# L-D5019-01-05.net
KiCad netlist of a schematic drawn in Altium Designer
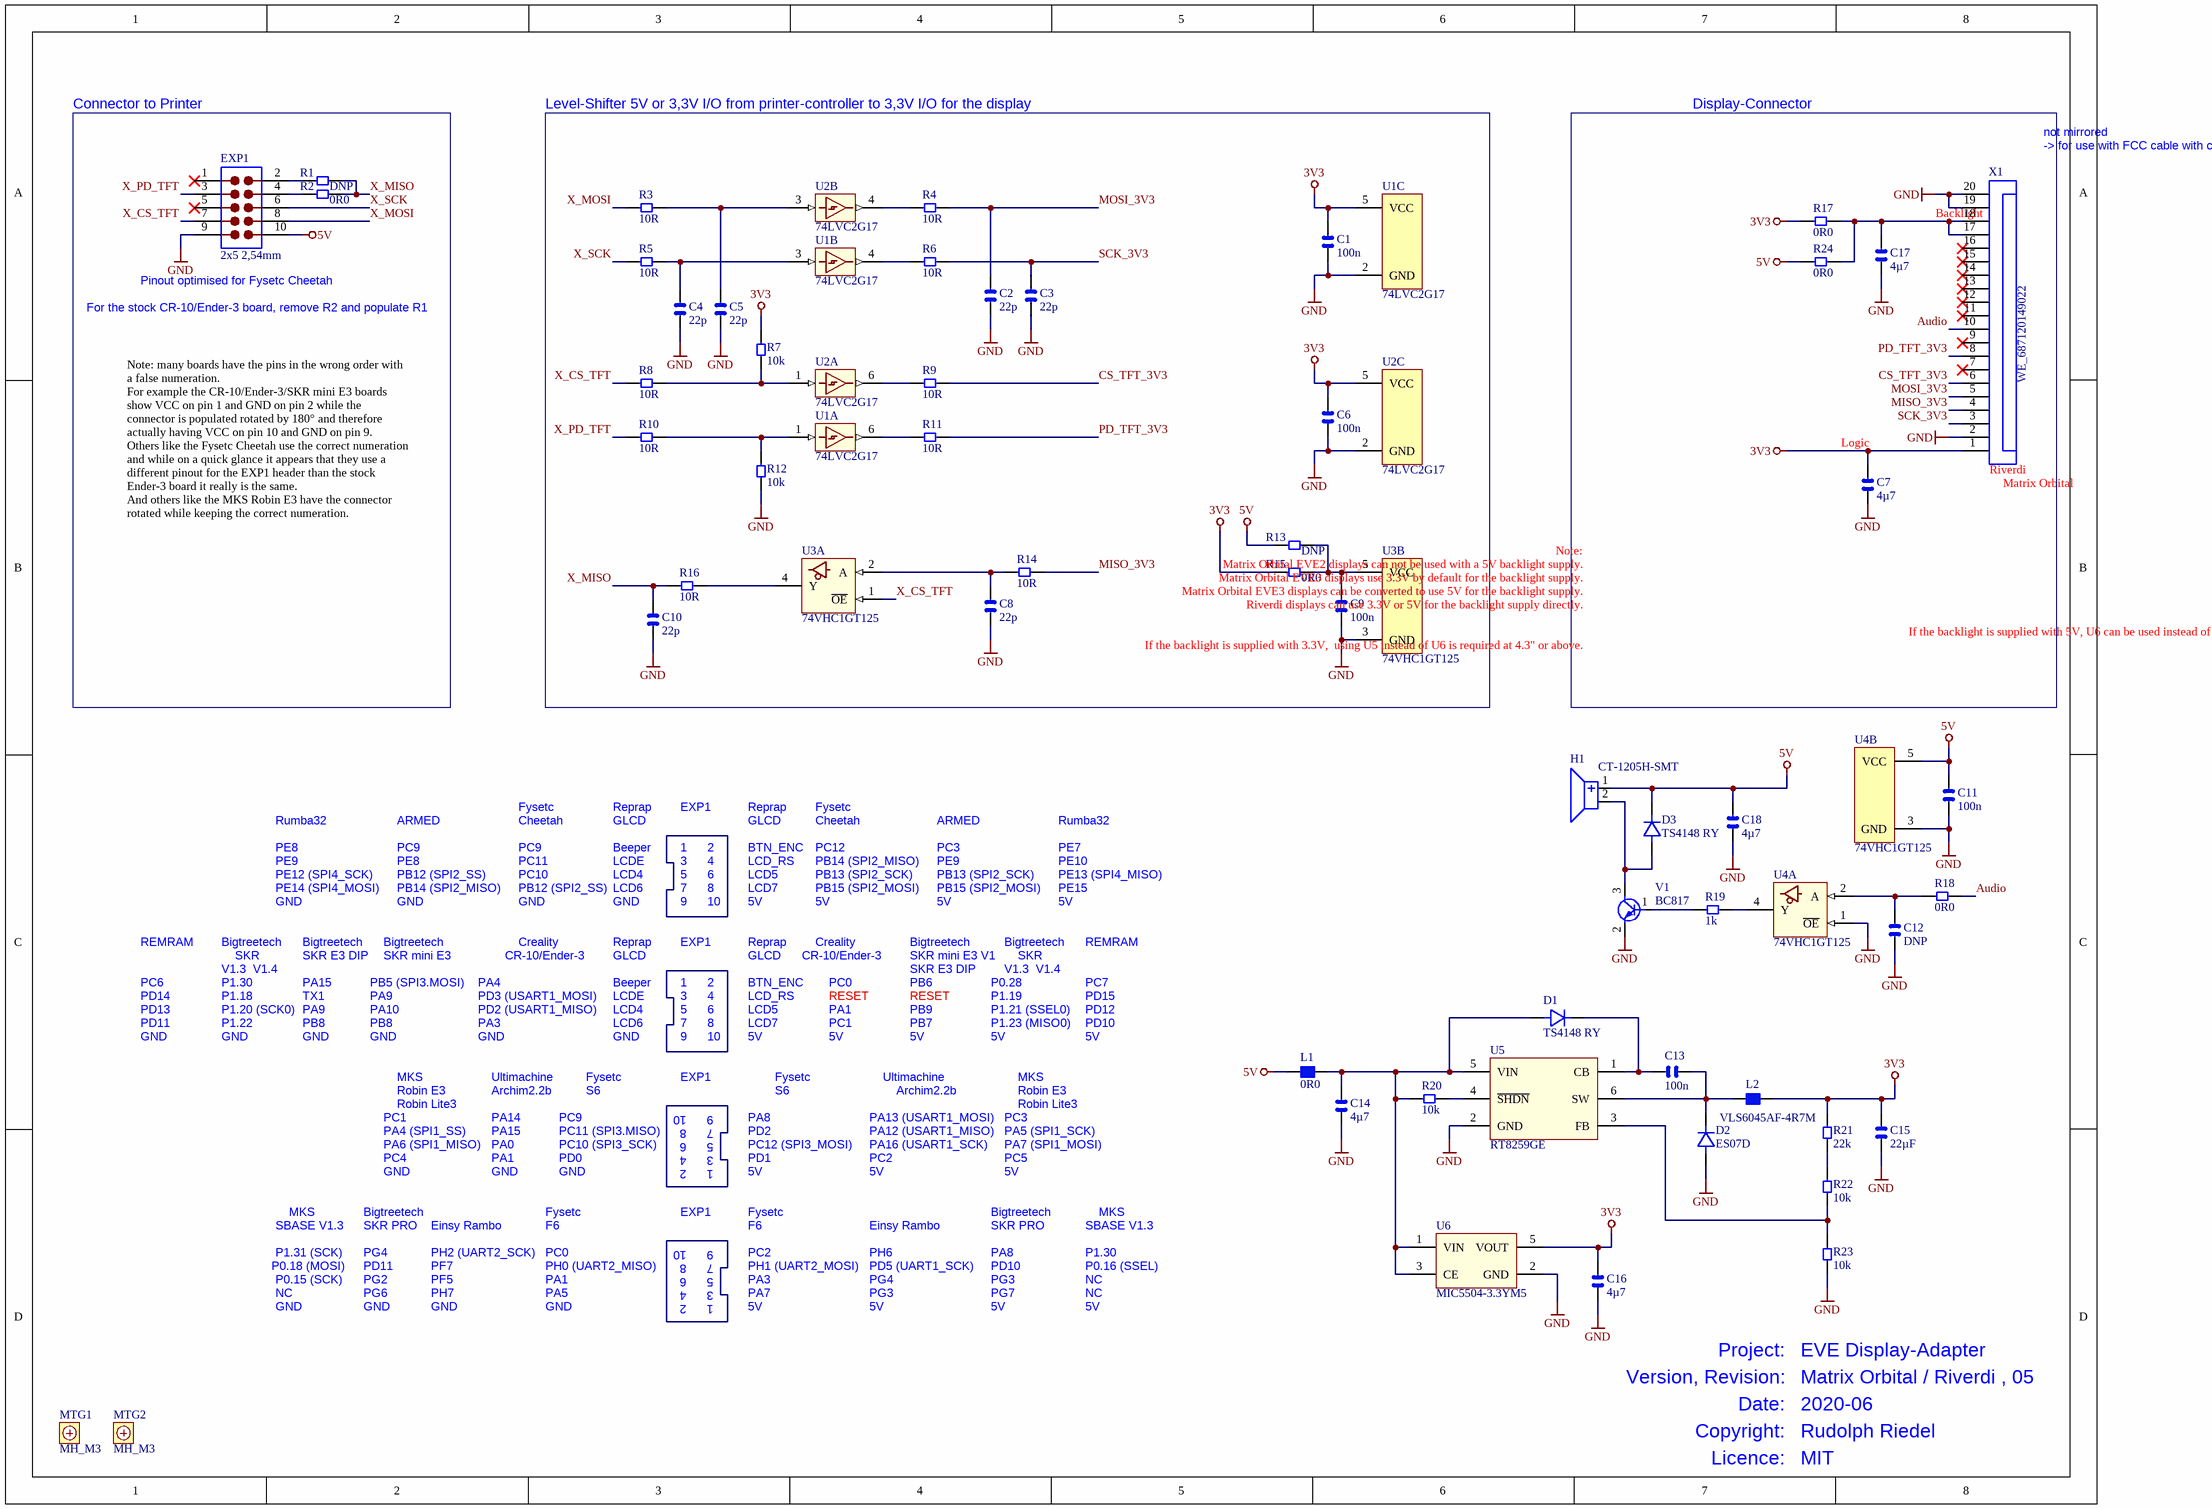
[diagram p0: L-D5019-01-05.SchDoc]

(export (version "E")
  (design (tool "Eeschema 10.0.6"))
  (components
    (comp (ref "C1")
      (value "100n")
      (footprint "CAPC2012X14L")
      (description "0805 Chip Capacitor")
      (fields (field (name "PART NUMBER") "CAPC_0805") (field (name "EDITOR") "rriedel"))
      (libsource (lib "HW-Labor_GF") (part "CAP_2_V2"))
    )
    (comp (ref "C2")
      (value "22p")
      (footprint "CAPC2012X14L")
      (description "0805 Chip Capacitor")
      (fields (field (name "PART NUMBER") "CAPC_0805") (field (name "EDITOR") "rriedel"))
      (libsource (lib "HW-Labor_GF") (part "CAP_2_V2"))
    )
    (comp (ref "C3")
      (value "22p")
      (footprint "CAPC2012X14L")
      (description "0805 Chip Capacitor")
      (fields (field (name "PART NUMBER") "CAPC_0805") (field (name "EDITOR") "rriedel"))
      (libsource (lib "HW-Labor_GF") (part "CAP_2_V2"))
    )
    (comp (ref "C4")
      (value "22p")
      (footprint "CAPC2012X14L")
      (description "0805 Chip Capacitor")
      (fields (field (name "PART NUMBER") "CAPC_0805") (field (name "EDITOR") "rriedel"))
      (libsource (lib "HW-Labor_GF") (part "CAP_2_V2"))
    )
    (comp (ref "C5")
      (value "22p")
      (footprint "CAPC2012X14L")
      (description "0805 Chip Capacitor")
      (fields (field (name "PART NUMBER") "CAPC_0805") (field (name "EDITOR") "rriedel"))
      (libsource (lib "HW-Labor_GF") (part "CAP_2_V2"))
    )
    (comp (ref "C6")
      (value "100n")
      (footprint "CAPC2012X14L")
      (description "0805 Chip Capacitor")
      (fields (field (name "PART NUMBER") "CAPC_0805") (field (name "EDITOR") "rriedel"))
      (libsource (lib "HW-Labor_GF") (part "CAP_2_V2"))
    )
    (comp (ref "C7")
      (value "4µ7")
      (footprint "CAPC2012X14L")
      (description "0805 Chip Capacitor")
      (fields (field (name "PART NUMBER") "CAPC_0805") (field (name "ERSTELLER") "rriedel"))
      (libsource (lib "HW-Labor_GF") (part "CAP_2_V2"))
    )
    (comp (ref "C8")
      (value "22p")
      (footprint "CAPC2012X14L")
      (description "0805 Chip Capacitor")
      (fields (field (name "PART NUMBER") "CAPC_0805") (field (name "EDITOR") "rriedel"))
      (libsource (lib "HW-Labor_GF") (part "CAP_2_V2"))
    )
    (comp (ref "C9")
      (value "100n")
      (footprint "CAPC2012X14L")
      (description "0805 Chip Capacitor")
      (fields (field (name "PART NUMBER") "CAPC_0805") (field (name "EDITOR") "rriedel"))
      (libsource (lib "HW-Labor_GF") (part "CAP_2_V2"))
    )
    (comp (ref "C10")
      (value "22p")
      (footprint "CAPC2012X14L")
      (description "0805 Chip Capacitor")
      (fields (field (name "PART NUMBER") "CAPC_0805") (field (name "EDITOR") "rriedel"))
      (libsource (lib "HW-Labor_GF") (part "CAP_2_V2"))
    )
    (comp (ref "C11")
      (value "100n")
      (footprint "CAPC2012X14L")
      (description "0805 Chip Capacitor")
      (fields (field (name "PART NUMBER") "CAPC_0805") (field (name "EDITOR") "rriedel"))
      (libsource (lib "HW-Labor_GF") (part "CAP_2_V2"))
    )
    (comp (ref "C12")
      (value "DNP")
      (footprint "CAPC2012X14L")
      (description "0805 Chip Capacitor")
      (fields (field (name "PART NUMBER") "CAPC_0805") (field (name "EDITOR") "rriedel"))
      (libsource (lib "HW-Labor_GF") (part "CAP_2_V2"))
    )
    (comp (ref "C13")
      (value "100n")
      (footprint "CAPC2012X14L")
      (description "0805 Chip Capacitor")
      (fields (field (name "PART NUMBER") "CAPC_0805") (field (name "EDITOR") "rriedel"))
      (libsource (lib "HW-Labor_GF") (part "CAP_2_V2"))
    )
    (comp (ref "C14")
      (value "4µ7")
      (footprint "CAPC2012X14L")
      (description "0805 Chip Capacitor")
      (fields (field (name "PART NUMBER") "CAPC_0805") (field (name "ERSTELLER") "rriedel"))
      (libsource (lib "HW-Labor_GF") (part "CAP_2_V2"))
    )
    (comp (ref "C15")
      (value "22µF")
      (footprint "CAPC3216X19N")
      (description "1206 Chip Capacitor")
      (fields (field (name "PART NUMBER") "CAPC_1206") (field (name "EDITOR") "rriedel"))
      (libsource (lib "HW-Labor_GF") (part "CAP_2_V2"))
    )
    (comp (ref "C16")
      (value "4µ7")
      (footprint "CAPC2012X14L")
      (description "0805 Chip Capacitor")
      (fields (field (name "PART NUMBER") "CAPC_0805") (field (name "ERSTELLER") "rriedel"))
      (libsource (lib "HW-Labor_GF") (part "CAP_2_V2"))
    )
    (comp (ref "C17")
      (value "4µ7")
      (footprint "CAPC2012X14L")
      (description "0805 Chip Capacitor")
      (fields (field (name "PART NUMBER") "CAPC_0805") (field (name "ERSTELLER") "rriedel"))
      (libsource (lib "HW-Labor_GF") (part "CAP_2_V2"))
    )
    (comp (ref "C18")
      (value "4µ7")
      (footprint "CAPC2012X14L")
      (description "0805 Chip Capacitor")
      (fields (field (name "PART NUMBER") "CAPC_0805") (field (name "ERSTELLER") "rriedel"))
      (libsource (lib "HW-Labor_GF") (part "CAP_2_V2"))
    )
    (comp (ref "D1")
      (value "TS4148 RY")
      (footprint "DIOC2012X10N")
      (description "Small Signal Diode IF 0.3A, VR 75V, 0805")
      (fields
        (field (name "PART NUMBER") "TSC_TS4148 RY")
        (field (name "MANUFACTURER") "TSC")
        (field (name "EDITOR") "rriedel")
      )
      (libsource (lib "HW-Labor_GF") (part "Diode_A2_K1"))
    )
    (comp (ref "D2")
      (value "ES07D")
      (footprint "DIOM2818X11N")
      (description "Ultrafast Rectifier Surface Mount,  IF 0.5A, VR 100V, DO-219AB, AEC-Q101")
      (fields (field (name "MANUFACTURER") "Vishay") (field (name "EDITOR") "rriedel"))
      (libsource (lib "HW-Labor_GF") (part "Diode_A2_K1"))
    )
    (comp (ref "D3")
      (value "TS4148 RY")
      (footprint "DIOC2012X10N")
      (description "Small Signal Diode IF 0.3A, VR 75V, 0805")
      (fields
        (field (name "PART NUMBER") "TSC_TS4148 RY")
        (field (name "MANUFACTURER") "TSC")
        (field (name "EDITOR") "rriedel")
      )
      (libsource (lib "HW-Labor_GF") (part "Diode_A2_K1"))
    )
    (comp (ref "EXP1")
      (value "2x5 2,54mm")
      (footprint "PINH_2x5_2_54mm_shroud")
      (description "Pin-Header 2,54 mm 2x5pins, shrouded")
      (fields (field (name "PART NUMBER") "PINH_2x5_2_54") (field (name "EDITOR") "rriedel"))
      (libsource (lib "HW-Labor_GF") (part "CONM_2x5_V2"))
    )
    (comp (ref "H1")
      (value "CT-1205H-SMT")
      (footprint "CT-1205H-SMT")
      (description "Speaker, Magnetic, 47R, 60mA, 88dBA, SMT, 12.8 x 12.8 mm,  height 10 mm")
      (fields
        (field (name "MANUFACTURER") "CUI")
        (field (name "DISTRIBUTOR_1_PART_NUMBER") "102-1266-1-ND")
        (field (name "EDITOR") "rriedel")
      )
      (libsource (lib "HW-Labor_GF") (part "Speaker"))
    )
    (comp (ref "L1")
      (value "0R0")
      (footprint "INDC2012X10L")
      (description "0805 Chip Inductor")
      (fields (field (name "PART NUMBER") "INDC_0805") (field (name "EDITOR") "rriedel"))
      (libsource (lib "HW-Labor_GF") (part "IND_2_V1"))
    )
    (comp (ref "L2")
      (value "VLS6045AF-4R7M")
      (footprint "PowerInductor_6x6")
      (description "4,7µH, shielded, 4,7A, 26mR")
      (fields
        (field (name "MANUFACTURER") "TDK")
        (field (name "DISTRIBUTOR_1_PART_NUMBER") "445-180835-1-ND")
        (field (name "EDITOR") "rriedel")
      )
      (libsource (lib "HW-Labor_GF") (part "IND_2_V1"))
    )
    (comp (ref "MTG1")
      (value "MH_M3")
      (footprint "HOLE_3_2MM")
      (description "Mounting-Hole for M3 screws")
      (fields (field (name "EDITOR") "rriedel"))
      (libsource (lib "HW-Labor_GF") (part "MTG_V1"))
    )
    (comp (ref "MTG2")
      (value "MH_M3")
      (footprint "HOLE_3_2MM")
      (description "Mounting-Hole for M3 screws")
      (fields (field (name "EDITOR") "rriedel"))
      (libsource (lib "HW-Labor_GF") (part "MTG_V1"))
    )
    (comp (ref "R1")
      (value "DNP")
      (footprint "RESC2012X06L")
      (description "0805 Chip Resistor")
      (fields (field (name "PART NUMBER") "RESC_0805") (field (name "EDITOR") "rriedel"))
      (libsource (lib "HW-Labor_GF") (part "RES_2_V2"))
    )
    (comp (ref "R2")
      (value "0R0")
      (footprint "RESC2012X06L")
      (description "0805 Chip Resistor")
      (fields (field (name "PART NUMBER") "RESC_0805") (field (name "EDITOR") "rriedel"))
      (libsource (lib "HW-Labor_GF") (part "RES_2_V2"))
    )
    (comp (ref "R3")
      (value "10R")
      (footprint "RESC2012X06L")
      (description "0805 Chip Resistor")
      (fields (field (name "PART NUMBER") "RESC_0805") (field (name "EDITOR") "rriedel"))
      (libsource (lib "HW-Labor_GF") (part "RES_2_V2"))
    )
    (comp (ref "R4")
      (value "10R")
      (footprint "RESC2012X06L")
      (description "0805 Chip Resistor")
      (fields (field (name "PART NUMBER") "RESC_0805") (field (name "EDITOR") "rriedel"))
      (libsource (lib "HW-Labor_GF") (part "RES_2_V2"))
    )
    (comp (ref "R5")
      (value "10R")
      (footprint "RESC2012X06L")
      (description "0805 Chip Resistor")
      (fields (field (name "PART NUMBER") "RESC_0805") (field (name "EDITOR") "rriedel"))
      (libsource (lib "HW-Labor_GF") (part "RES_2_V2"))
    )
    (comp (ref "R6")
      (value "10R")
      (footprint "RESC2012X06L")
      (description "0805 Chip Resistor")
      (fields (field (name "PART NUMBER") "RESC_0805") (field (name "EDITOR") "rriedel"))
      (libsource (lib "HW-Labor_GF") (part "RES_2_V2"))
    )
    (comp (ref "R7")
      (value "10k")
      (footprint "RESC2012X06L")
      (description "0805 Chip Resistor")
      (fields (field (name "PART NUMBER") "RESC_0805") (field (name "EDITOR") "rriedel"))
      (libsource (lib "HW-Labor_GF") (part "RES_2_V2"))
    )
    (comp (ref "R8")
      (value "10R")
      (footprint "RESC2012X06L")
      (description "0805 Chip Resistor")
      (fields (field (name "PART NUMBER") "RESC_0805") (field (name "EDITOR") "rriedel"))
      (libsource (lib "HW-Labor_GF") (part "RES_2_V2"))
    )
    (comp (ref "R9")
      (value "10R")
      (footprint "RESC2012X06L")
      (description "0805 Chip Resistor")
      (fields (field (name "PART NUMBER") "RESC_0805") (field (name "EDITOR") "rriedel"))
      (libsource (lib "HW-Labor_GF") (part "RES_2_V2"))
    )
    (comp (ref "R10")
      (value "10R")
      (footprint "RESC2012X06L")
      (description "0805 Chip Resistor")
      (fields (field (name "PART NUMBER") "RESC_0805") (field (name "EDITOR") "rriedel"))
      (libsource (lib "HW-Labor_GF") (part "RES_2_V2"))
    )
    (comp (ref "R11")
      (value "10R")
      (footprint "RESC2012X06L")
      (description "0805 Chip Resistor")
      (fields (field (name "PART NUMBER") "RESC_0805") (field (name "EDITOR") "rriedel"))
      (libsource (lib "HW-Labor_GF") (part "RES_2_V2"))
    )
    (comp (ref "R12")
      (value "10k")
      (footprint "RESC2012X06L")
      (description "0805 Chip Resistor")
      (fields (field (name "PART NUMBER") "RESC_0805") (field (name "EDITOR") "rriedel"))
      (libsource (lib "HW-Labor_GF") (part "RES_2_V2"))
    )
    (comp (ref "R13")
      (value "DNP")
      (footprint "RESC2012X06L")
      (description "0805 Chip Resistor")
      (fields (field (name "PART NUMBER") "RESC_0805") (field (name "EDITOR") "rriedel"))
      (libsource (lib "HW-Labor_GF") (part "RES_2_V2"))
    )
    (comp (ref "R14")
      (value "10R")
      (footprint "RESC2012X06L")
      (description "0805 Chip Resistor")
      (fields (field (name "PART NUMBER") "RESC_0805") (field (name "EDITOR") "rriedel"))
      (libsource (lib "HW-Labor_GF") (part "RES_2_V2"))
    )
    (comp (ref "R15")
      (value "0R0")
      (footprint "RESC2012X06L")
      (description "0805 Chip Resistor")
      (fields (field (name "PART NUMBER") "RESC_0805") (field (name "EDITOR") "rriedel"))
      (libsource (lib "HW-Labor_GF") (part "RES_2_V2"))
    )
    (comp (ref "R16")
      (value "10R")
      (footprint "RESC2012X06L")
      (description "0805 Chip Resistor")
      (fields (field (name "PART NUMBER") "RESC_0805") (field (name "EDITOR") "rriedel"))
      (libsource (lib "HW-Labor_GF") (part "RES_2_V2"))
    )
    (comp (ref "R17")
      (value "0R0")
      (footprint "RESC2012X06L")
      (description "0805 Chip Resistor")
      (fields (field (name "PART NUMBER") "RESC_0805") (field (name "EDITOR") "rriedel"))
      (libsource (lib "HW-Labor_GF") (part "RES_2_V2"))
    )
    (comp (ref "R18")
      (value "0R0")
      (footprint "RESC2012X06L")
      (description "0805 Chip Resistor")
      (fields (field (name "PART NUMBER") "RESC_0805") (field (name "EDITOR") "rriedel"))
      (libsource (lib "HW-Labor_GF") (part "RES_2_V2"))
    )
    (comp (ref "R19")
      (value "1k")
      (footprint "RESC2012X06L")
      (description "0805 Chip Resistor")
      (fields (field (name "PART NUMBER") "RESC_0805") (field (name "EDITOR") "rriedel"))
      (libsource (lib "HW-Labor_GF") (part "RES_2_V2"))
    )
    (comp (ref "R20")
      (value "10k")
      (footprint "RESC2012X06L")
      (description "0805 Chip Resistor")
      (fields (field (name "PART NUMBER") "RESC_0805") (field (name "EDITOR") "rriedel"))
      (libsource (lib "HW-Labor_GF") (part "RES_2_V2"))
    )
    (comp (ref "R21")
      (value "22k")
      (footprint "RESC2012X06L")
      (description "0805 Chip Resistor")
      (fields (field (name "PART NUMBER") "RESC_0805") (field (name "EDITOR") "rriedel"))
      (libsource (lib "HW-Labor_GF") (part "RES_2_V2"))
    )
    (comp (ref "R22")
      (value "10k")
      (footprint "RESC2012X06L")
      (description "0805 Chip Resistor")
      (fields (field (name "PART NUMBER") "RESC_0805") (field (name "EDITOR") "rriedel"))
      (libsource (lib "HW-Labor_GF") (part "RES_2_V2"))
    )
    (comp (ref "R23")
      (value "10k")
      (footprint "RESC2012X06L")
      (description "0805 Chip Resistor")
      (fields (field (name "PART NUMBER") "RESC_0805") (field (name "EDITOR") "rriedel"))
      (libsource (lib "HW-Labor_GF") (part "RES_2_V2"))
    )
    (comp (ref "R24")
      (value "0R0")
      (footprint "RESC2012X06L")
      (description "0805 Chip Resistor")
      (fields (field (name "PART NUMBER") "RESC_0805") (field (name "EDITOR") "rriedel"))
      (libsource (lib "HW-Labor_GF") (part "RES_2_V2"))
    )
    (comp (ref "U1")
      (value "74LVC2G17")
      (footprint "SOT95P280X110-6N")
      (description "Dual Schmitt-Trigger Buffer with 5.5V tolerant inputs")
      (fields
        (field (name "MANUFACTURER") "TI")
        (field (name "DISTRIBUTOR_1_PART_NUMBER") "296-SN74LVC2G17DBVRCT-ND‎")
        (field (name "EDITOR") "rriedel")
      )
      (libsource (lib "HW-Labor_GF") (part "74LVC2G17"))
    )
    (comp (ref "U2")
      (value "74LVC2G17")
      (footprint "SOT95P280X110-6N")
      (description "Dual Schmitt-Trigger Buffer with 5.5V tolerant inputs")
      (fields
        (field (name "MANUFACTURER") "TI")
        (field (name "DISTRIBUTOR_1_PART_NUMBER") "296-SN74LVC2G17DBVRCT-ND‎")
        (field (name "EDITOR") "rriedel")
      )
      (libsource (lib "HW-Labor_GF") (part "74LVC2G17"))
    )
    (comp (ref "U3")
      (value "74VHC1GT125")
      (footprint "SOT95P280X110-5N")
      (description "1x Buffer with OE; 3-state,Level Shifter 3,3V to 5V and 5V to 3.3V")
      (fields
        (field (name "MANUFACTURER") "ON Semiconductor")
        (field (name "DISTRIBUTOR_1_PART_NUMBER") "1703291")
        (field (name "EDITOR") "rriedel")
      )
      (libsource (lib "") (part "74LVC1G125G_1"))
    )
    (comp (ref "U4")
      (value "74VHC1GT125")
      (footprint "SOT95P280X110-5N")
      (description "1x Buffer with OE; 3-state,Level Shifter 3,3V to 5V and 5V to 3.3V")
      (fields
        (field (name "MANUFACTURER") "ON Semiconductor")
        (field (name "DISTRIBUTOR_1_PART_NUMBER") "1703291")
        (field (name "EDITOR") "rriedel")
      )
      (libsource (lib "") (part "74LVC1G125G_1"))
    )
    (comp (ref "U5")
      (value "RT8259GE")
      (footprint "SOT95P280X110-6N")
      (description "Step-Down DC/DC Regulator, 24V, 1.2A, 1,4MHz")
      (fields
        (field (name "MANUFACTURER") "Richtek")
        (field (name "DISTRIBUTOR_1_PART_NUMBER") "1028-1497-1-ND")
        (field (name "EDITOR") "rriedel")
      )
      (libsource (lib "HW-Labor_GF") (part "StepDown_SOT23-6"))
    )
    (comp (ref "U6")
      (value "MIC5504-3.3YM5")
      (footprint "SOT95P280X110-5N")
      (description "300 mA LDO,  Vin=2,5V…5,5V, Vout= 3,3V, -40°C..125°C")
      (fields
        (field (name "MANUFACTURER") "Microchip")
        (field (name "DISTRIBUTOR_1_PART_NUMBER") "2510377")
        (field (name "EDITOR") "rriedel")
      )
      (libsource (lib "HW-Labor_GF") (part "LDO_SOT23-5"))
    )
    (comp (ref "V1")
      (value "BC817")
      (footprint "SOT95P280X110-3N")
      (description "NPN Transistor SOT23, 1=B, 2=C, 3=E")
      (fields (field (name "EDITOR") "rriedel"))
      (libsource (lib "HW-Labor_GF") (part "NPN_B1_C2_E3"))
    )
    (comp (ref "X1")
      (value "WE_687120149022")
      (footprint "WE_687120149022")
      (description "20pin WR-FPC 0.50 mm SMT ZIF Horizontal - Bottom Contact")
      (fields
        (field (name "MANUFACTURER") "Wuerth")
        (field (name "DISTRIBUTOR_1_PART_NUMBER") "732-6002-1-ND")
        (field (name "EDITOR") "rriedel")
      )
      (libsource (lib "HW-Labor_GF") (part "FPC_20"))
    )
  )
  (nets
    (net (code "1") (name "/Audio") (class "Default")
      (node (ref "R18") (pin "2") (pinfunction "2_2") (pintype "passive"))
      (node (ref "X1") (pin "10") (pinfunction "10_10") (pintype "passive"))
    )
    (net (code "2") (name "/CS_TFT_3V3") (class "Default")
      (node (ref "R9") (pin "2") (pinfunction "2_2") (pintype "passive"))
      (node (ref "X1") (pin "6") (pinfunction "6_6") (pintype "passive"))
    )
    (net (code "3") (name "/MISO_3V3") (class "Default")
      (node (ref "R14") (pin "2") (pinfunction "2_2") (pintype "passive"))
      (node (ref "X1") (pin "4") (pinfunction "4_4") (pintype "passive"))
    )
    (net (code "4") (name "/MOSI_3V3") (class "Default")
      (node (ref "C2") (pin "2") (pinfunction "2_2") (pintype "passive"))
      (node (ref "R4") (pin "2") (pinfunction "2_2") (pintype "passive"))
      (node (ref "X1") (pin "5") (pinfunction "5_5") (pintype "passive"))
    )
    (net (code "5") (name "/PD_TFT_3V3") (class "Default")
      (node (ref "R11") (pin "2") (pinfunction "2_2") (pintype "passive"))
      (node (ref "X1") (pin "8") (pinfunction "8_8") (pintype "passive"))
    )
    (net (code "6") (name "/SCK_3V3") (class "Default")
      (node (ref "C3") (pin "2") (pinfunction "2_2") (pintype "passive"))
      (node (ref "R6") (pin "2") (pinfunction "2_2") (pintype "passive"))
      (node (ref "X1") (pin "3") (pinfunction "3_3") (pintype "passive"))
    )
    (net (code "7") (name "/X_CS_TFT") (class "Default")
      (node (ref "EXP1") (pin "7") (pinfunction "7_7") (pintype "passive"))
      (node (ref "R8") (pin "1") (pinfunction "1_1") (pintype "passive"))
      (node (ref "U3") (pin "1") (pinfunction "~{OE}_1") (pintype "input"))
    )
    (net (code "8") (name "/X_MISO") (class "Default")
      (node (ref "C10") (pin "2") (pinfunction "2_2") (pintype "passive"))
      (node (ref "R1") (pin "2") (pinfunction "2_2") (pintype "passive"))
      (node (ref "R16") (pin "1") (pinfunction "1_1") (pintype "passive"))
      (node (ref "R2") (pin "2") (pinfunction "2_2") (pintype "passive"))
    )
    (net (code "9") (name "/X_MOSI") (class "Default")
      (node (ref "EXP1") (pin "8") (pinfunction "8_8") (pintype "passive"))
      (node (ref "R3") (pin "1") (pinfunction "1_1") (pintype "passive"))
    )
    (net (code "10") (name "/X_PD_TFT") (class "Default")
      (node (ref "EXP1") (pin "3") (pinfunction "3_3") (pintype "passive"))
      (node (ref "R10") (pin "1") (pinfunction "1_1") (pintype "passive"))
    )
    (net (code "11") (name "/X_SCK") (class "Default")
      (node (ref "EXP1") (pin "6") (pinfunction "6_6") (pintype "passive"))
      (node (ref "R5") (pin "1") (pinfunction "1_1") (pintype "passive"))
    )
    (net (code "12") (name "3V3") (class "Default")
      (node (ref "C1") (pin "2") (pinfunction "2_2") (pintype "passive"))
      (node (ref "C15") (pin "2") (pinfunction "2_2") (pintype "passive"))
      (node (ref "C16") (pin "2") (pinfunction "2_2") (pintype "passive"))
      (node (ref "C6") (pin "2") (pinfunction "2_2") (pintype "passive"))
      (node (ref "C7") (pin "2") (pinfunction "2_2") (pintype "passive"))
      (node (ref "L2") (pin "2") (pinfunction "2_2") (pintype "passive"))
      (node (ref "R15") (pin "1") (pinfunction "1_1") (pintype "passive"))
      (node (ref "R17") (pin "1") (pinfunction "1_1") (pintype "passive"))
      (node (ref "R21") (pin "2") (pinfunction "2_2") (pintype "passive"))
      (node (ref "R7") (pin "2") (pinfunction "2_2") (pintype "passive"))
      (node (ref "U1") (pin "5") (pinfunction "VCC_5") (pintype "power_in"))
      (node (ref "U2") (pin "5") (pinfunction "VCC_5") (pintype "power_in"))
      (node (ref "U6") (pin "5") (pinfunction "VOUT_5") (pintype "passive"))
      (node (ref "X1") (pin "1") (pinfunction "1_1") (pintype "passive"))
    )
    (net (code "13") (name "5V") (class "Default")
      (node (ref "C11") (pin "2") (pinfunction "2_2") (pintype "passive"))
      (node (ref "C18") (pin "2") (pinfunction "2_2") (pintype "passive"))
      (node (ref "D3") (pin "1") (pinfunction "1_1") (pintype "passive"))
      (node (ref "EXP1") (pin "10") (pinfunction "10_10") (pintype "passive"))
      (node (ref "H1") (pin "1") (pinfunction "1_1") (pintype "passive"))
      (node (ref "L1") (pin "1") (pinfunction "1_1") (pintype "passive"))
      (node (ref "R13") (pin "1") (pinfunction "1_1") (pintype "passive"))
      (node (ref "R24") (pin "1") (pinfunction "1_1") (pintype "passive"))
      (node (ref "U4") (pin "5") (pinfunction "VCC_5") (pintype "passive"))
    )
    (net (code "14") (name "GND") (class "Default")
      (node (ref "C1") (pin "1") (pinfunction "1_1") (pintype "passive"))
      (node (ref "C10") (pin "1") (pinfunction "1_1") (pintype "passive"))
      (node (ref "C11") (pin "1") (pinfunction "1_1") (pintype "passive"))
      (node (ref "C12") (pin "1") (pinfunction "1_1") (pintype "passive"))
      (node (ref "C14") (pin "1") (pinfunction "1_1") (pintype "passive"))
      (node (ref "C15") (pin "1") (pinfunction "1_1") (pintype "passive"))
      (node (ref "C16") (pin "1") (pinfunction "1_1") (pintype "passive"))
      (node (ref "C17") (pin "1") (pinfunction "1_1") (pintype "passive"))
      (node (ref "C18") (pin "1") (pinfunction "1_1") (pintype "passive"))
      (node (ref "C2") (pin "1") (pinfunction "1_1") (pintype "passive"))
      (node (ref "C3") (pin "1") (pinfunction "1_1") (pintype "passive"))
      (node (ref "C4") (pin "1") (pinfunction "1_1") (pintype "passive"))
      (node (ref "C5") (pin "1") (pinfunction "1_1") (pintype "passive"))
      (node (ref "C6") (pin "1") (pinfunction "1_1") (pintype "passive"))
      (node (ref "C7") (pin "1") (pinfunction "1_1") (pintype "passive"))
      (node (ref "C8") (pin "1") (pinfunction "1_1") (pintype "passive"))
      (node (ref "C9") (pin "1") (pinfunction "1_1") (pintype "passive"))
      (node (ref "D2") (pin "2") (pinfunction "2_2") (pintype "passive"))
      (node (ref "EXP1") (pin "9") (pinfunction "9_9") (pintype "passive"))
      (node (ref "R12") (pin "1") (pinfunction "1_1") (pintype "passive"))
      (node (ref "R23") (pin "1") (pinfunction "1_1") (pintype "passive"))
      (node (ref "U1") (pin "2") (pinfunction "GND_2") (pintype "power_in"))
      (node (ref "U2") (pin "2") (pinfunction "GND_2") (pintype "power_in"))
      (node (ref "U3") (pin "3") (pinfunction "GND_3") (pintype "passive"))
      (node (ref "U4") (pin "1") (pinfunction "~{OE}_1") (pintype "input"))
      (node (ref "U4") (pin "3") (pinfunction "GND_3") (pintype "passive"))
      (node (ref "U5") (pin "2") (pinfunction "GND_2") (pintype "power_in"))
      (node (ref "U6") (pin "2") (pinfunction "GND_2") (pintype "passive"))
      (node (ref "V1") (pin "2") (pinfunction "2_2") (pintype "passive"))
      (node (ref "X1") (pin "19") (pinfunction "19_19") (pintype "passive"))
      (node (ref "X1") (pin "2") (pinfunction "2_2") (pintype "passive"))
      (node (ref "X1") (pin "20") (pinfunction "20_20") (pintype "passive"))
    )
    (net (code "15") (name "Net-(C17-Pad2)") (class "Default")
      (node (ref "C17") (pin "2") (pinfunction "2_2") (pintype "passive"))
      (node (ref "R17") (pin "2") (pinfunction "2_2") (pintype "passive"))
      (node (ref "R24") (pin "2") (pinfunction "2_2") (pintype "passive"))
      (node (ref "X1") (pin "17") (pinfunction "17_17") (pintype "passive"))
      (node (ref "X1") (pin "18") (pinfunction "18_18") (pintype "passive"))
    )
    (net (code "16") (name "Net-(D3-Pad2)") (class "Default")
      (node (ref "D3") (pin "2") (pinfunction "2_2") (pintype "passive"))
      (node (ref "H1") (pin "2") (pinfunction "2_2") (pintype "passive"))
      (node (ref "V1") (pin "3") (pinfunction "3_3") (pintype "passive"))
    )
    (net (code "17") (name "Net-(EXP1-Pad2)") (class "Default")
      (node (ref "EXP1") (pin "2") (pinfunction "2_2") (pintype "passive"))
      (node (ref "R1") (pin "1") (pinfunction "1_1") (pintype "passive"))
    )
    (net (code "18") (name "Net-(EXP1-Pad4)") (class "Default")
      (node (ref "EXP1") (pin "4") (pinfunction "4_4") (pintype "passive"))
      (node (ref "R2") (pin "1") (pinfunction "1_1") (pintype "passive"))
    )
    (net (code "19") (name "Net-(R19-Pad2)") (class "Default")
      (node (ref "R19") (pin "2") (pinfunction "2_2") (pintype "passive"))
      (node (ref "V1") (pin "1") (pinfunction "1_1") (pintype "passive"))
    )
    (net (code "20") (name "Net-(R21-Pad1)") (class "Default")
      (node (ref "R21") (pin "1") (pinfunction "1_1") (pintype "passive"))
      (node (ref "R22") (pin "2") (pinfunction "2_2") (pintype "passive"))
    )
    (net (code "21") (name "Net-(U1A-1A)") (class "Default")
      (node (ref "R10") (pin "2") (pinfunction "2_2") (pintype "passive"))
      (node (ref "R12") (pin "2") (pinfunction "2_2") (pintype "passive"))
      (node (ref "U1") (pin "1") (pinfunction "1A_1") (pintype "input"))
    )
    (net (code "22") (name "Net-(U1A-1Y)") (class "Default")
      (node (ref "R11") (pin "1") (pinfunction "1_1") (pintype "passive"))
      (node (ref "U1") (pin "6") (pinfunction "1Y_6") (pintype "output"))
    )
    (net (code "23") (name "Net-(U1B-2A)") (class "Default")
      (node (ref "C4") (pin "2") (pinfunction "2_2") (pintype "passive"))
      (node (ref "R5") (pin "2") (pinfunction "2_2") (pintype "passive"))
      (node (ref "U1") (pin "3") (pinfunction "2A_3") (pintype "input"))
    )
    (net (code "24") (name "Net-(U1B-2Y)") (class "Default")
      (node (ref "R6") (pin "1") (pinfunction "1_1") (pintype "passive"))
      (node (ref "U1") (pin "4") (pinfunction "2Y_4") (pintype "output"))
    )
    (net (code "25") (name "Net-(U2A-1A)") (class "Default")
      (node (ref "R7") (pin "1") (pinfunction "1_1") (pintype "passive"))
      (node (ref "R8") (pin "2") (pinfunction "2_2") (pintype "passive"))
      (node (ref "U2") (pin "1") (pinfunction "1A_1") (pintype "input"))
    )
    (net (code "26") (name "Net-(U2A-1Y)") (class "Default")
      (node (ref "R9") (pin "1") (pinfunction "1_1") (pintype "passive"))
      (node (ref "U2") (pin "6") (pinfunction "1Y_6") (pintype "output"))
    )
    (net (code "27") (name "Net-(U2B-2A)") (class "Default")
      (node (ref "C5") (pin "2") (pinfunction "2_2") (pintype "passive"))
      (node (ref "R3") (pin "2") (pinfunction "2_2") (pintype "passive"))
      (node (ref "U2") (pin "3") (pinfunction "2A_3") (pintype "input"))
    )
    (net (code "28") (name "Net-(U2B-2Y)") (class "Default")
      (node (ref "R4") (pin "1") (pinfunction "1_1") (pintype "passive"))
      (node (ref "U2") (pin "4") (pinfunction "2Y_4") (pintype "output"))
    )
    (net (code "29") (name "Net-(U3A-A)") (class "Default")
      (node (ref "C8") (pin "2") (pinfunction "2_2") (pintype "passive"))
      (node (ref "R14") (pin "1") (pinfunction "1_1") (pintype "passive"))
      (node (ref "U3") (pin "2") (pinfunction "A_2") (pintype "input"))
    )
    (net (code "30") (name "Net-(U3A-Y)") (class "Default")
      (node (ref "R16") (pin "2") (pinfunction "2_2") (pintype "passive"))
      (node (ref "U3") (pin "4") (pinfunction "Y_4") (pintype "tri_state"))
    )
    (net (code "31") (name "Net-(U3B-VCC)") (class "Default")
      (node (ref "C9") (pin "2") (pinfunction "2_2") (pintype "passive"))
      (node (ref "R13") (pin "2") (pinfunction "2_2") (pintype "passive"))
      (node (ref "R15") (pin "2") (pinfunction "2_2") (pintype "passive"))
      (node (ref "U3") (pin "5") (pinfunction "VCC_5") (pintype "passive"))
    )
    (net (code "32") (name "Net-(U4A-A)") (class "Default")
      (node (ref "C12") (pin "2") (pinfunction "2_2") (pintype "passive"))
      (node (ref "R18") (pin "1") (pinfunction "1_1") (pintype "passive"))
      (node (ref "U4") (pin "2") (pinfunction "A_2") (pintype "input"))
    )
    (net (code "33") (name "Net-(U4A-Y)") (class "Default")
      (node (ref "R19") (pin "1") (pinfunction "1_1") (pintype "passive"))
      (node (ref "U4") (pin "4") (pinfunction "Y_4") (pintype "tri_state"))
    )
    (net (code "34") (name "Net-(U5-CB)") (class "Default")
      (node (ref "C13") (pin "1") (pinfunction "1_1") (pintype "passive"))
      (node (ref "D1") (pin "1") (pinfunction "1_1") (pintype "passive"))
      (node (ref "U5") (pin "1") (pinfunction "CB_1") (pintype "passive"))
    )
    (net (code "35") (name "Net-(U5-FB)") (class "Default")
      (node (ref "R22") (pin "1") (pinfunction "1_1") (pintype "passive"))
      (node (ref "R23") (pin "2") (pinfunction "2_2") (pintype "passive"))
      (node (ref "U5") (pin "3") (pinfunction "FB_3") (pintype "passive"))
    )
    (net (code "36") (name "Net-(U5-SW)") (class "Default")
      (node (ref "C13") (pin "2") (pinfunction "2_2") (pintype "passive"))
      (node (ref "D2") (pin "1") (pinfunction "1_1") (pintype "passive"))
      (node (ref "L2") (pin "1") (pinfunction "1_1") (pintype "passive"))
      (node (ref "U5") (pin "6") (pinfunction "SW_6") (pintype "passive"))
    )
    (net (code "37") (name "Net-(U5-VIN)") (class "Default")
      (node (ref "C14") (pin "2") (pinfunction "2_2") (pintype "passive"))
      (node (ref "D1") (pin "2") (pinfunction "2_2") (pintype "passive"))
      (node (ref "L1") (pin "2") (pinfunction "2_2") (pintype "passive"))
      (node (ref "R20") (pin "1") (pinfunction "1_1") (pintype "passive"))
      (node (ref "U5") (pin "5") (pinfunction "VIN_5") (pintype "power_in"))
      (node (ref "U6") (pin "1") (pinfunction "VIN_1") (pintype "passive"))
      (node (ref "U6") (pin "3") (pinfunction "CE_3") (pintype "passive"))
    )
    (net (code "38") (name "Net-(U5-~{SHDN})") (class "Default")
      (node (ref "R20") (pin "2") (pinfunction "2_2") (pintype "passive"))
      (node (ref "U5") (pin "4") (pinfunction "~{SHDN}_4") (pintype "passive"))
    )
    (net (code "39") (name "unconnected-(EXP1-Pad1)") (class "Default")
      (node (ref "EXP1") (pin "1") (pinfunction "1_1") (pintype "passive+no_connect"))
    )
    (net (code "40") (name "unconnected-(EXP1-Pad5)") (class "Default")
      (node (ref "EXP1") (pin "5") (pinfunction "5_5") (pintype "passive+no_connect"))
    )
    (net (code "41") (name "unconnected-(X1-Pad7)") (class "Default")
      (node (ref "X1") (pin "7") (pinfunction "7_7") (pintype "passive+no_connect"))
    )
    (net (code "42") (name "unconnected-(X1-Pad9)") (class "Default")
      (node (ref "X1") (pin "9") (pinfunction "9_9") (pintype "passive+no_connect"))
    )
    (net (code "43") (name "unconnected-(X1-Pad11)") (class "Default")
      (node (ref "X1") (pin "11") (pinfunction "11_11") (pintype "passive+no_connect"))
    )
    (net (code "44") (name "unconnected-(X1-Pad12)") (class "Default")
      (node (ref "X1") (pin "12") (pinfunction "12_12") (pintype "passive+no_connect"))
    )
    (net (code "45") (name "unconnected-(X1-Pad13)") (class "Default")
      (node (ref "X1") (pin "13") (pinfunction "13_13") (pintype "passive+no_connect"))
    )
    (net (code "46") (name "unconnected-(X1-Pad14)") (class "Default")
      (node (ref "X1") (pin "14") (pinfunction "14_14") (pintype "passive+no_connect"))
    )
    (net (code "47") (name "unconnected-(X1-Pad15)") (class "Default")
      (node (ref "X1") (pin "15") (pinfunction "15_15") (pintype "passive+no_connect"))
    )
    (net (code "48") (name "unconnected-(X1-Pad16)") (class "Default")
      (node (ref "X1") (pin "16") (pinfunction "16_16") (pintype "passive+no_connect"))
    )
  )
)
